# LowTemp.net
KiCad netlist of a schematic drawn in EAGLE
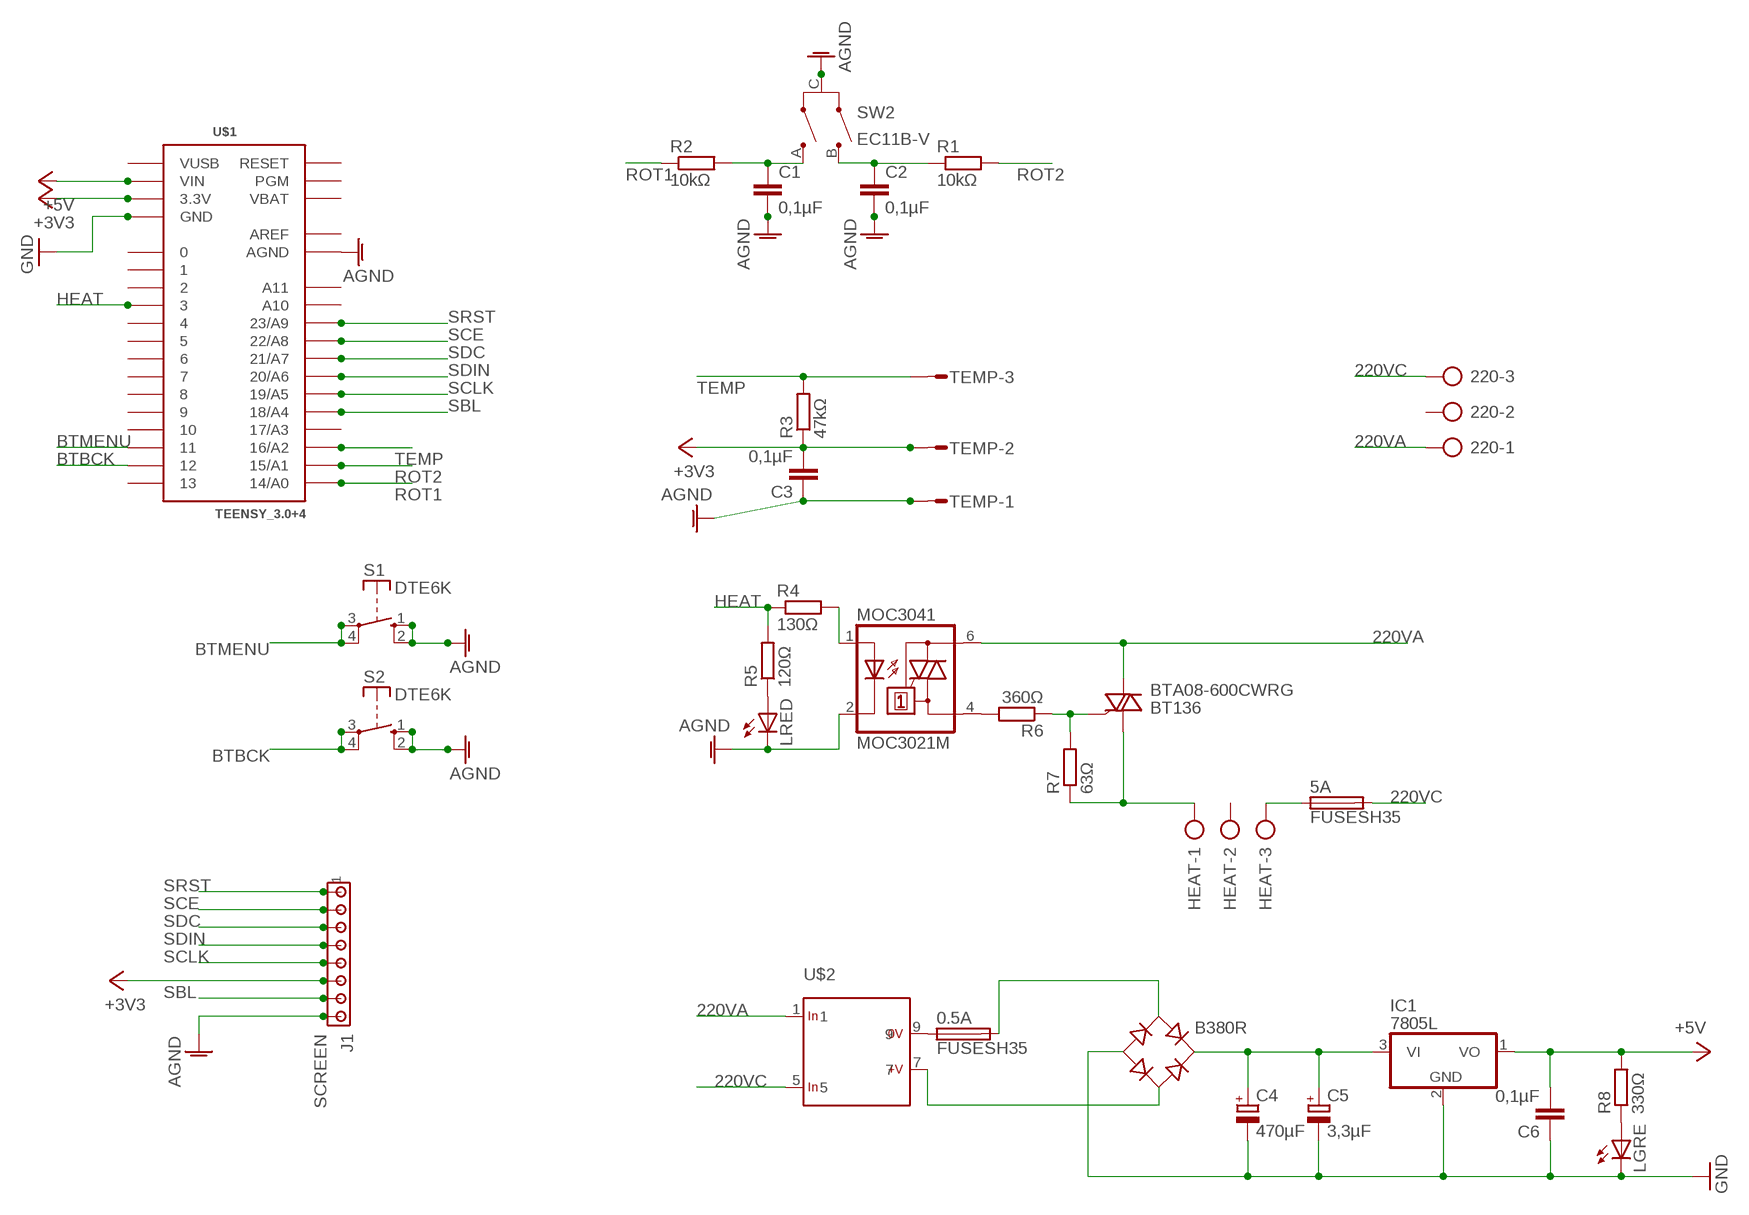
[diagram p0: schematic, sheet 1]

(export (version "E")
  (design (tool "Eeschema 10.0.6"))
  (components
    (comp (ref "0.5A")
      (value "FUSESH35")
      (footprint "eagle-import:SH25")
      (libsource (lib "eagle-import") (part "FUSESH35"))
    )
    (comp (ref "5A")
      (value "FUSESH35")
      (footprint "eagle-import:SH25")
      (libsource (lib "eagle-import") (part "FUSESH35"))
    )
    (comp (ref "220")
      (value "AK500/3-H")
      (footprint "eagle-import:AK500_3-H")
      (libsource (lib "eagle-import") (part "AK500/3-H"))
    )
    (comp (ref "B380R")
      (value "RB1A")
      (footprint "eagle-import:RB1A")
      (libsource (lib "eagle-import") (part "RB1A"))
    )
    (comp (ref "BTA08-600CWRG")
      (value "BT136")
      (footprint "eagle-import:TO220AB")
      (libsource (lib "eagle-import") (part "BT136"))
    )
    (comp (ref "C1")
      (value "0,1µF")
      (footprint "eagle-import:C050-025X075")
      (libsource (lib "eagle-import") (part "C-EU050-025X075"))
    )
    (comp (ref "C2")
      (value "0,1µF")
      (footprint "eagle-import:C050-025X075")
      (libsource (lib "eagle-import") (part "C-EU050-025X075"))
    )
    (comp (ref "C3")
      (value "0,1µF")
      (footprint "eagle-import:C050-025X075")
      (libsource (lib "eagle-import") (part "C-EU050-025X075"))
    )
    (comp (ref "C4")
      (value "470µF")
      (footprint "eagle-import:E5-8,5")
      (libsource (lib "eagle-import") (part "CPOL-EUE5-8.5"))
    )
    (comp (ref "C5")
      (value "3,3µF")
      (footprint "eagle-import:TT2D4")
      (libsource (lib "eagle-import") (part "CPOL-EUTT2D4"))
    )
    (comp (ref "C6")
      (value "0,1µF")
      (footprint "eagle-import:C050-025X075")
      (libsource (lib "eagle-import") (part "C-EU050-025X075"))
    )
    (comp (ref "HEAT")
      (value "AK500/3-H")
      (footprint "eagle-import:AK500_3-H")
      (libsource (lib "eagle-import") (part "AK500/3-H"))
    )
    (comp (ref "IC1")
      (value "7805L")
      (footprint "eagle-import:TO92")
      (libsource (lib "eagle-import") (part "78L05"))
    )
    (comp (ref "J1")
      (value "SCREEN")
      (footprint "eagle-import:10X08MTA")
      (libsource (lib "eagle-import") (part "MTA08-100"))
    )
    (comp (ref "LGRE")
      (value "LED5MM")
      (footprint "eagle-import:LED5MM")
      (libsource (lib "eagle-import") (part "LED5MM"))
    )
    (comp (ref "LRED")
      (value "LED5MM")
      (footprint "eagle-import:LED5MM")
      (libsource (lib "eagle-import") (part "LED5MM"))
    )
    (comp (ref "MOC3041")
      (value "MOC3021M")
      (footprint "eagle-import:DIL06")
      (fields (field (name "MF") "FAIRCHILD SEMICONDUCTOR") (field (name "MPN") "MOC3021-M"))
      (libsource (lib "eagle-import") (part "MOC30M21"))
    )
    (comp (ref "R1")
      (value "10kΩ")
      (footprint "eagle-import:0207_10")
      (libsource (lib "eagle-import") (part "R-EU_0207/10"))
    )
    (comp (ref "R2")
      (value "10kΩ")
      (footprint "eagle-import:0207_10")
      (libsource (lib "eagle-import") (part "R-EU_0207/10"))
    )
    (comp (ref "R3")
      (value "47kΩ")
      (footprint "eagle-import:0207_10")
      (libsource (lib "eagle-import") (part "R-EU_0207/10"))
    )
    (comp (ref "R4")
      (value "130Ω")
      (footprint "eagle-import:0207_10")
      (libsource (lib "eagle-import") (part "R-EU_0207/10"))
    )
    (comp (ref "R5")
      (value "120Ω")
      (footprint "eagle-import:0207_10")
      (libsource (lib "eagle-import") (part "R-EU_0207/10"))
    )
    (comp (ref "R6")
      (value "360Ω")
      (footprint "eagle-import:0207_10")
      (libsource (lib "eagle-import") (part "R-EU_0207/10"))
    )
    (comp (ref "R7")
      (value "63Ω")
      (footprint "eagle-import:0207_10")
      (libsource (lib "eagle-import") (part "R-EU_0207/10"))
    )
    (comp (ref "R8")
      (value "330Ω")
      (footprint "eagle-import:0207_10")
      (libsource (lib "eagle-import") (part "R-EU_0207/10"))
    )
    (comp (ref "S1")
      (value "DTE6K")
      (footprint "eagle-import:DTE6K")
      (libsource (lib "eagle-import") (part "DTE6K"))
    )
    (comp (ref "S2")
      (value "DTE6K")
      (footprint "eagle-import:DTE6K")
      (libsource (lib "eagle-import") (part "DTE6K"))
    )
    (comp (ref "SW2")
      (value "EC11B-V")
      (footprint "eagle-import:EC11B-V")
      (libsource (lib "eagle-import") (part "EC11B-V"))
    )
    (comp (ref "TEMP")
      (value "L03P")
      (footprint "eagle-import:L03P")
      (libsource (lib "eagle-import") (part "L03P"))
    )
    (comp (ref "U$1")
      (value "TEENSY_3.0+4")
      (footprint "eagle-import:TEENSY_3.0+4")
      (libsource (lib "eagle-import") (part "TEENSY_3.0+4"))
    )
    (comp (ref "U$2")
      (value "SINGLE")
      (footprint "eagle-import:1")
      (libsource (lib "eagle-import") (part "SINGLE"))
    )
  )
  (nets
    (net (code "1") (name "+3V3") (class "Default")
      (node (ref "C3") (pin "2") (pinfunction "2_2") (pintype "passive"))
      (node (ref "J1") (pin "6") (pinfunction "6_6") (pintype "passive"))
      (node (ref "R3") (pin "1") (pinfunction "1_1") (pintype "passive"))
      (node (ref "TEMP") (pin "2") (pinfunction "S_2") (pintype "passive"))
      (node (ref "U$1") (pin "3.3V") (pinfunction "3.3V_3.3V") (pintype "power_in"))
      (node (ref "U$1") (pin "3.3V1") (pinfunction "3.3V_3.3V1") (pintype "power_in"))
    )
    (net (code "2") (name "+5V") (class "Default")
      (node (ref "C6") (pin "2") (pinfunction "2_2") (pintype "passive"))
      (node (ref "IC1") (pin "1") (pinfunction "VO_1") (pintype "passive"))
      (node (ref "R8") (pin "2") (pinfunction "2_2") (pintype "passive"))
      (node (ref "U$1") (pin "VIN") (pinfunction "VIN_VIN") (pintype "power_in"))
    )
    (net (code "3") (name "/220VA") (class "Default")
      (node (ref "220") (pin "1") (pinfunction "KL_1") (pintype "passive"))
      (node (ref "BTA08-600CWRG") (pin "2") (pinfunction "A2_2") (pintype "passive"))
      (node (ref "MOC3041") (pin "6") (pinfunction "A2_6") (pintype "passive"))
      (node (ref "U$2") (pin "1") (pinfunction "1_1") (pintype "input"))
    )
    (net (code "4") (name "/220VC") (class "Default")
      (node (ref "220") (pin "3") (pinfunction "KL_3") (pintype "passive"))
      (node (ref "5A") (pin "2") (pinfunction "2_2") (pintype "passive"))
      (node (ref "U$2") (pin "5") (pinfunction "5_5") (pintype "input"))
    )
    (net (code "5") (name "/AREF") (class "Default")
      (node (ref "U$1") (pin "AREF") (pinfunction "AREF_AREF") (pintype "power_in"))
    )
    (net (code "6") (name "/BTBCK") (class "Default")
      (node (ref "S2") (pin "3") (pinfunction "P_3") (pintype "passive"))
      (node (ref "S2") (pin "4") (pinfunction "P_4") (pintype "passive"))
      (node (ref "U$1") (pin "12") (pinfunction "12_12") (pintype "bidirectional"))
    )
    (net (code "7") (name "/BTMENU") (class "Default")
      (node (ref "S1") (pin "3") (pinfunction "P_3") (pintype "passive"))
      (node (ref "S1") (pin "4") (pinfunction "P_4") (pintype "passive"))
      (node (ref "U$1") (pin "11") (pinfunction "11_11") (pintype "bidirectional"))
    )
    (net (code "8") (name "/HEAT") (class "Default")
      (node (ref "R4") (pin "1") (pinfunction "1_1") (pintype "passive"))
      (node (ref "R5") (pin "2") (pinfunction "2_2") (pintype "passive"))
      (node (ref "U$1") (pin "3") (pinfunction "3_3") (pintype "bidirectional"))
    )
    (net (code "9") (name "/ROT1") (class "Default")
      (node (ref "R2") (pin "1") (pinfunction "1_1") (pintype "passive"))
      (node (ref "U$1") (pin "14/A0") (pinfunction "14/A0_14/A0") (pintype "bidirectional"))
    )
    (net (code "10") (name "/ROT2") (class "Default")
      (node (ref "R1") (pin "2") (pinfunction "2_2") (pintype "passive"))
      (node (ref "U$1") (pin "15/A1") (pinfunction "15/A1_15/A1") (pintype "bidirectional"))
    )
    (net (code "11") (name "/SBL") (class "Default")
      (node (ref "J1") (pin "7") (pinfunction "7_7") (pintype "passive"))
      (node (ref "U$1") (pin "18/A4") (pinfunction "18/A4_18/A4") (pintype "bidirectional"))
    )
    (net (code "12") (name "/SCE") (class "Default")
      (node (ref "J1") (pin "2") (pinfunction "2_2") (pintype "passive"))
      (node (ref "U$1") (pin "22/A8") (pinfunction "22/A8_22/A8") (pintype "bidirectional"))
    )
    (net (code "13") (name "/SCLK") (class "Default")
      (node (ref "J1") (pin "5") (pinfunction "5_5") (pintype "passive"))
      (node (ref "U$1") (pin "19/A5") (pinfunction "19/A5_19/A5") (pintype "bidirectional"))
    )
    (net (code "14") (name "/SDC") (class "Default")
      (node (ref "J1") (pin "3") (pinfunction "3_3") (pintype "passive"))
      (node (ref "U$1") (pin "21/A7") (pinfunction "21/A7_21/A7") (pintype "bidirectional"))
    )
    (net (code "15") (name "/SDIN") (class "Default")
      (node (ref "J1") (pin "4") (pinfunction "4_4") (pintype "passive"))
      (node (ref "U$1") (pin "20/A6") (pinfunction "20/A6_20/A6") (pintype "bidirectional"))
    )
    (net (code "16") (name "/SRST") (class "Default")
      (node (ref "J1") (pin "1") (pinfunction "1_1") (pintype "passive"))
      (node (ref "U$1") (pin "23/A9") (pinfunction "23/A9_23/A9") (pintype "bidirectional"))
    )
    (net (code "17") (name "/TEMP") (class "Default")
      (node (ref "R3") (pin "2") (pinfunction "2_2") (pintype "passive"))
      (node (ref "TEMP") (pin "3") (pinfunction "S_3") (pintype "passive"))
      (node (ref "U$1") (pin "16/A2") (pinfunction "16/A2_16/A2") (pintype "bidirectional"))
    )
    (net (code "18") (name "/VBAT") (class "Default")
      (node (ref "U$1") (pin "VBAT") (pinfunction "VBAT_VBAT") (pintype "power_in"))
    )
    (net (code "19") (name "/VUSB") (class "Default")
      (node (ref "U$1") (pin "VUSB") (pinfunction "VUSB_VUSB") (pintype "power_in"))
    )
    (net (code "20") (name "AGND") (class "Default")
      (node (ref "C1") (pin "2") (pinfunction "2_2") (pintype "passive"))
      (node (ref "C2") (pin "2") (pinfunction "2_2") (pintype "passive"))
      (node (ref "C3") (pin "1") (pinfunction "1_1") (pintype "passive"))
      (node (ref "J1") (pin "8") (pinfunction "8_8") (pintype "passive"))
      (node (ref "LRED") (pin "K") (pinfunction "C_K") (pintype "passive"))
      (node (ref "MOC3041") (pin "2") (pinfunction "C_2") (pintype "passive"))
      (node (ref "S1") (pin "1") (pinfunction "S_1") (pintype "passive"))
      (node (ref "S1") (pin "2") (pinfunction "S_2") (pintype "passive"))
      (node (ref "S2") (pin "1") (pinfunction "S_1") (pintype "passive"))
      (node (ref "S2") (pin "2") (pinfunction "S_2") (pintype "passive"))
      (node (ref "SW2") (pin "C") (pinfunction "C_C") (pintype "passive"))
      (node (ref "TEMP") (pin "1") (pinfunction "S_1") (pintype "passive"))
      (node (ref "U$1") (pin "AGND") (pinfunction "AGND_AGND") (pintype "power_in"))
    )
    (net (code "21") (name "GND") (class "Default")
      (node (ref "B380R") (pin "-") (pinfunction "-_-") (pintype "passive"))
      (node (ref "C4") (pin "-") (pinfunction "-_-") (pintype "passive"))
      (node (ref "C5") (pin "-") (pinfunction "-_-") (pintype "passive"))
      (node (ref "C6") (pin "1") (pinfunction "1_1") (pintype "passive"))
      (node (ref "IC1") (pin "2") (pinfunction "GND_2") (pintype "passive"))
      (node (ref "LGRE") (pin "K") (pinfunction "C_K") (pintype "passive"))
      (node (ref "U$1") (pin "GND") (pinfunction "GND_GND") (pintype "power_in"))
      (node (ref "U$1") (pin "GND1") (pinfunction "GND_GND1") (pintype "power_in"))
    )
    (net (code "22") (name "Net-(0.5A-Pad1)") (class "Default")
      (node (ref "0.5A") (pin "1") (pinfunction "1_1") (pintype "passive"))
      (node (ref "U$2") (pin "9") (pinfunction "9_9") (pintype "output"))
    )
    (net (code "23") (name "Net-(0.5A-Pad2)") (class "Default")
      (node (ref "0.5A") (pin "2") (pinfunction "2_2") (pintype "passive"))
      (node (ref "B380R") (pin "AC1") (pinfunction "AC1_AC1") (pintype "passive"))
    )
    (net (code "24") (name "Net-(B380R-PadAC2)") (class "Default")
      (node (ref "B380R") (pin "AC2") (pinfunction "AC2_AC2") (pintype "passive"))
      (node (ref "U$2") (pin "7") (pinfunction "7_7") (pintype "output"))
    )
    (net (code "25") (name "Net-(BTA08-600CWRG-A1)") (class "Default")
      (node (ref "BTA08-600CWRG") (pin "1") (pinfunction "A1_1") (pintype "passive"))
      (node (ref "HEAT") (pin "1") (pinfunction "KL_1") (pintype "passive"))
      (node (ref "R7") (pin "1") (pinfunction "1_1") (pintype "passive"))
    )
    (net (code "26") (name "Net-(BTA08-600CWRG-G)") (class "Default")
      (node (ref "BTA08-600CWRG") (pin "3") (pinfunction "G_3") (pintype "passive"))
      (node (ref "R6") (pin "1") (pinfunction "1_1") (pintype "passive"))
      (node (ref "R7") (pin "2") (pinfunction "2_2") (pintype "passive"))
    )
    (net (code "27") (name "Net-(C1-Pad1)") (class "Default")
      (node (ref "C1") (pin "1") (pinfunction "1_1") (pintype "passive"))
      (node (ref "R2") (pin "2") (pinfunction "2_2") (pintype "passive"))
      (node (ref "SW2") (pin "A") (pinfunction "A_A") (pintype "passive"))
    )
    (net (code "28") (name "Net-(C2-Pad1)") (class "Default")
      (node (ref "C2") (pin "1") (pinfunction "1_1") (pintype "passive"))
      (node (ref "R1") (pin "1") (pinfunction "1_1") (pintype "passive"))
      (node (ref "SW2") (pin "B") (pinfunction "B_B") (pintype "passive"))
    )
    (net (code "29") (name "Net-(HEATC-KL)") (class "Default")
      (node (ref "5A") (pin "1") (pinfunction "1_1") (pintype "passive"))
      (node (ref "HEAT") (pin "3") (pinfunction "KL_3") (pintype "passive"))
    )
    (net (code "30") (name "Net-(IC1-VI)") (class "Default")
      (node (ref "B380R") (pin "+") (pinfunction "+_+") (pintype "passive"))
      (node (ref "C4") (pin "+") (pinfunction "+_+") (pintype "passive"))
      (node (ref "C5") (pin "+") (pinfunction "+_+") (pintype "passive"))
      (node (ref "IC1") (pin "3") (pinfunction "VI_3") (pintype "input"))
    )
    (net (code "31") (name "Net-(LGRE-PadA)") (class "Default")
      (node (ref "LGRE") (pin "A") (pinfunction "A_A") (pintype "passive"))
      (node (ref "R8") (pin "1") (pinfunction "1_1") (pintype "passive"))
    )
    (net (code "32") (name "Net-(LRED-PadA)") (class "Default")
      (node (ref "LRED") (pin "A") (pinfunction "A_A") (pintype "passive"))
      (node (ref "R5") (pin "1") (pinfunction "1_1") (pintype "passive"))
    )
    (net (code "33") (name "Net-(MOC3041-A)") (class "Default")
      (node (ref "MOC3041") (pin "1") (pinfunction "A_1") (pintype "passive"))
      (node (ref "R4") (pin "2") (pinfunction "2_2") (pintype "passive"))
    )
    (net (code "34") (name "Net-(MOC3041-A1)") (class "Default")
      (node (ref "MOC3041") (pin "4") (pinfunction "A1_4") (pintype "passive"))
      (node (ref "R6") (pin "2") (pinfunction "2_2") (pintype "passive"))
    )
    (net (code "35") (name "unconnected-(220B-KL-Pad2)") (class "Default")
      (node (ref "220") (pin "2") (pinfunction "KL_2") (pintype "passive"))
    )
    (net (code "36") (name "unconnected-(HEATB-KL-Pad2)") (class "Default")
      (node (ref "HEAT") (pin "2") (pinfunction "KL_2") (pintype "passive"))
    )
    (net (code "37") (name "unconnected-(U$1-Pad0)") (class "Default")
      (node (ref "U$1") (pin "0") (pinfunction "0_0") (pintype "bidirectional"))
    )
    (net (code "38") (name "unconnected-(U$1-Pad1)") (class "Default")
      (node (ref "U$1") (pin "1") (pinfunction "1_1") (pintype "bidirectional"))
    )
    (net (code "39") (name "unconnected-(U$1-Pad2)") (class "Default")
      (node (ref "U$1") (pin "2") (pinfunction "2_2") (pintype "bidirectional"))
    )
    (net (code "40") (name "unconnected-(U$1-Pad4)") (class "Default")
      (node (ref "U$1") (pin "4") (pinfunction "4_4") (pintype "bidirectional"))
    )
    (net (code "41") (name "unconnected-(U$1-Pad5)") (class "Default")
      (node (ref "U$1") (pin "5") (pinfunction "5_5") (pintype "bidirectional"))
    )
    (net (code "42") (name "unconnected-(U$1-Pad6)") (class "Default")
      (node (ref "U$1") (pin "6") (pinfunction "6_6") (pintype "bidirectional"))
    )
    (net (code "43") (name "unconnected-(U$1-Pad7)") (class "Default")
      (node (ref "U$1") (pin "7") (pinfunction "7_7") (pintype "bidirectional"))
    )
    (net (code "44") (name "unconnected-(U$1-Pad8)") (class "Default")
      (node (ref "U$1") (pin "8") (pinfunction "8_8") (pintype "bidirectional"))
    )
    (net (code "45") (name "unconnected-(U$1-Pad9)") (class "Default")
      (node (ref "U$1") (pin "9") (pinfunction "9_9") (pintype "bidirectional"))
    )
    (net (code "46") (name "unconnected-(U$1-Pad10)") (class "Default")
      (node (ref "U$1") (pin "10") (pinfunction "10_10") (pintype "bidirectional"))
    )
    (net (code "47") (name "unconnected-(U$1-Pad13)") (class "Default")
      (node (ref "U$1") (pin "13") (pinfunction "13_13") (pintype "bidirectional"))
    )
    (net (code "48") (name "unconnected-(U$1-Pad17{slash}A3)") (class "Default")
      (node (ref "U$1") (pin "17/A3") (pinfunction "17/A3_17/A3") (pintype "bidirectional"))
    )
    (net (code "49") (name "unconnected-(U$1-PadA10)") (class "Default")
      (node (ref "U$1") (pin "A10") (pinfunction "A10_A10") (pintype "bidirectional"))
    )
    (net (code "50") (name "unconnected-(U$1-PadA11)") (class "Default")
      (node (ref "U$1") (pin "A11") (pinfunction "A11_A11") (pintype "bidirectional"))
    )
    (net (code "51") (name "unconnected-(U$1-PadPGM)") (class "Default")
      (node (ref "U$1") (pin "PGM") (pinfunction "PGM_PGM") (pintype "bidirectional"))
    )
    (net (code "52") (name "unconnected-(U$1-PadRESET)") (class "Default")
      (node (ref "U$1") (pin "RESET") (pinfunction "RESET_RESET") (pintype "bidirectional"))
    )
  )
)
